# radio.net
KiCad netlist of a schematic drawn in Altium Designer
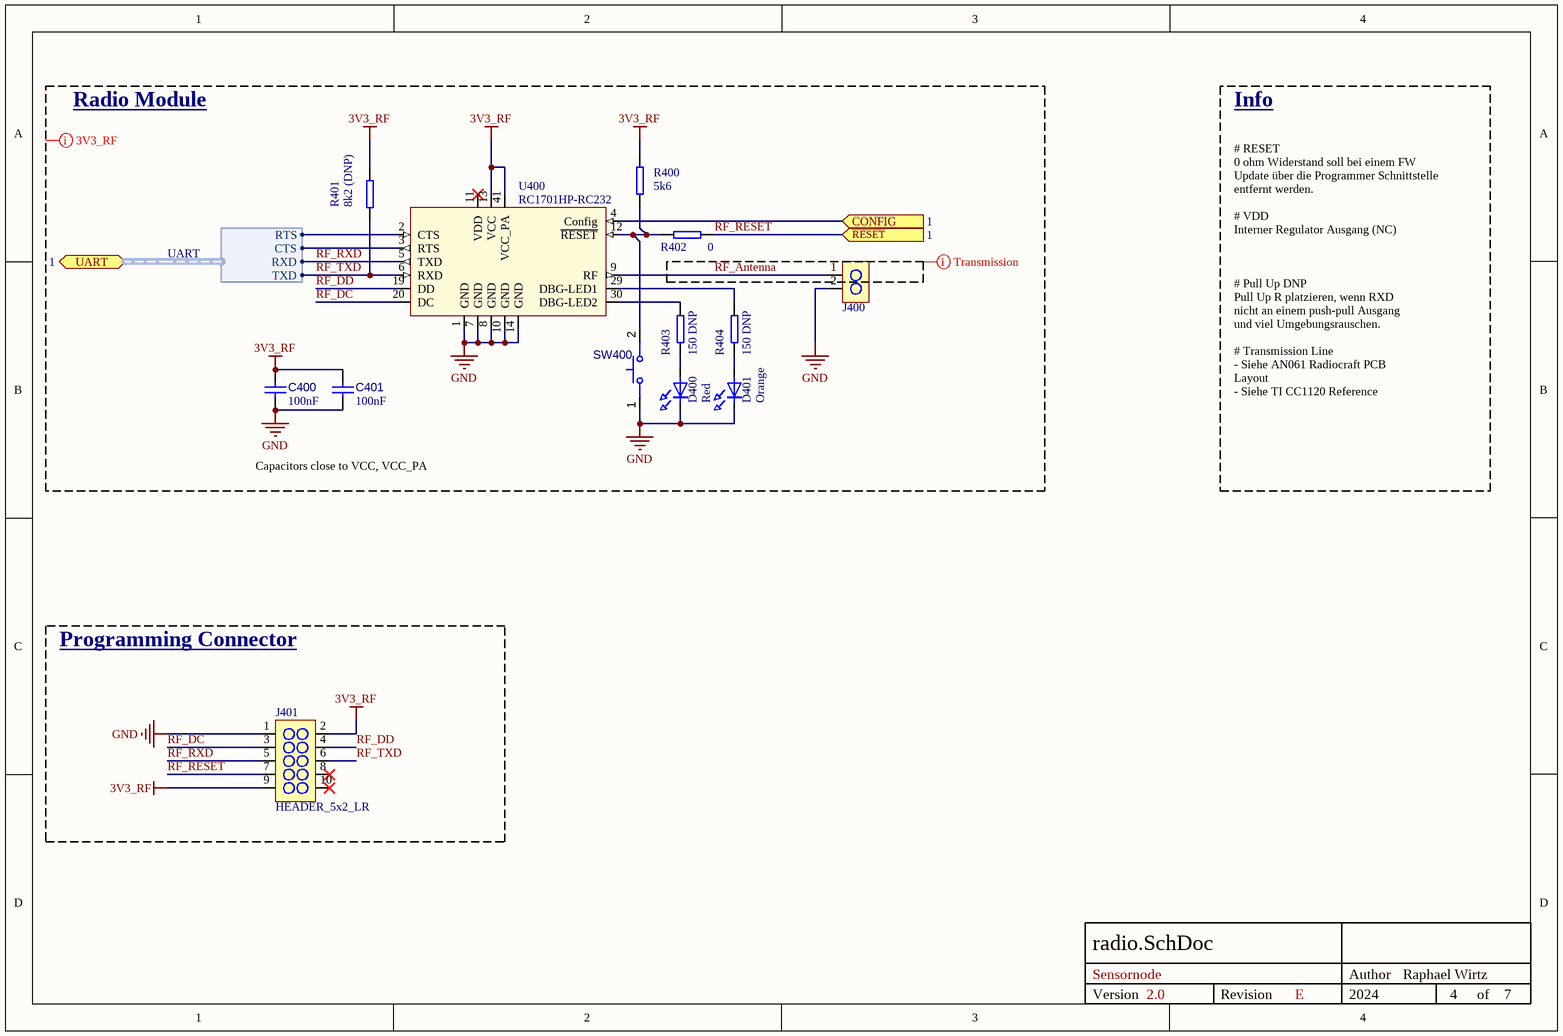
[diagram p0: radio.SchDoc]

(export (version "E")
  (design (tool "Eeschema 10.0.6"))
  (components
    (comp (ref "C400")
      (value "100nF")
      (footprint "sensornode:0603")
      (fields
        (field (name "TOLERANCE") "10%")
        (field (name "MANUFACTURER") "TDK")
        (field (name "MANUFACTURER PART NUMBER") "C1005X6S0J105K050BC")
      )
      (libsource (lib "sensornode_v2") (part "C"))
    )
    (comp (ref "C401")
      (value "100nF")
      (footprint "sensornode:0603")
      (fields
        (field (name "TOLERANCE") "10%")
        (field (name "MANUFACTURER") "TDK")
        (field (name "MANUFACTURER PART NUMBER") "C1005X6S0J105K050BC")
      )
      (libsource (lib "sensornode_v2") (part "C"))
    )
    (comp (ref "D400")
      (value "Red")
      (footprint "sensornode:0603-Diode")
      (libsource (lib "sensornode_v2") (part "LED_1"))
    )
    (comp (ref "D401")
      (value "Orange")
      (footprint "sensornode:0603-Diode")
      (libsource (lib "sensornode_v2") (part "LED_1"))
    )
    (comp (ref "J400")
      (value "RF_LPRS_x2")
      (footprint "sensornode:SMARACONNECTOR")
      (libsource (lib "sensornode_v2") (part "RF_LPRS_x2"))
    )
    (comp (ref "J401")
      (value "HEADER_5x2_LR")
      (footprint "sensornode:HEADER_SMD_1.27")
      (libsource (lib "sensornode_v2") (part "HEADER_5x2_LR"))
    )
    (comp (ref "R400")
      (value "5k6")
      (footprint "sensornode:0603")
      (description "Normaler Widerstand")
      (libsource (lib "sensornode_v2") (part "R?"))
    )
    (comp (ref "R401")
      (value "8k2 (DNP)")
      (footprint "sensornode:0603")
      (description "Normaler Widerstand")
      (libsource (lib "sensornode_v2") (part "R?"))
    )
    (comp (ref "R402")
      (value "0")
      (footprint "sensornode:0603")
      (description "Normaler Widerstand")
      (libsource (lib "sensornode_v2") (part "R?"))
    )
    (comp (ref "R403")
      (value "150 DNP")
      (footprint "sensornode:0603")
      (description "Normaler Widerstand")
      (libsource (lib "sensornode_v2") (part "R?"))
    )
    (comp (ref "R404")
      (value "150 DNP")
      (footprint "sensornode:0603")
      (description "Normaler Widerstand")
      (libsource (lib "sensornode_v2") (part "R?"))
    )
    (comp (ref "SW400")
      (value "B3U-1000P-B")
      (footprint "OMRON-B3U-1000P-2-B_V")
      (libsource (lib "Hochschule Luzern T&A") (part "CMP-00164-6"))
    )
    (comp (ref "U400")
      (value "RC1701HP-RC232")
      (footprint "sensornode:RF_RC1701HP")
      (libsource (lib "sensornode_v2") (part "RC1701HP-RC232"))
    )
  )
  (nets
    (net (code "2") (name "/CONFIG") (class "Default")
      (node (ref "U400") (pin "4") (pinfunction "Config_4") (pintype "input"))
    )
    (net (code "3") (name "/CTS") (class "Default")
      (node (ref "U400") (pin "3") (pinfunction "RTS_3") (pintype "output"))
    )
    (net (code "4") (name "/RF_Antenna") (class "Default")
      (node (ref "J400") (pin "1") (pinfunction "1_1") (pintype "passive"))
      (node (ref "U400") (pin "9") (pinfunction "RF_9") (pintype "output"))
    )
    (net (code "5") (name "/RF_DC") (class "Default")
      (node (ref "J401") (pin "3") (pinfunction "3_3") (pintype "passive"))
      (node (ref "U400") (pin "20") (pinfunction "DC_20") (pintype "passive"))
    )
    (net (code "6") (name "/RF_DD") (class "Default")
      (node (ref "J401") (pin "4") (pinfunction "4_4") (pintype "passive"))
      (node (ref "U400") (pin "19") (pinfunction "DD_19") (pintype "passive"))
    )
    (net (code "7") (name "/RF_RESET") (class "Default")
      (node (ref "J401") (pin "7") (pinfunction "7_7") (pintype "passive"))
      (node (ref "R402") (pin "1") (pintype "passive"))
    )
    (net (code "8") (name "/RF_RXD") (class "Default")
      (node (ref "J401") (pin "5") (pinfunction "5_5") (pintype "passive"))
      (node (ref "U400") (pin "5") (pinfunction "TXD_5") (pintype "output"))
    )
    (net (code "9") (name "/RF_TXD") (class "Default")
      (node (ref "J401") (pin "6") (pinfunction "6_6") (pintype "passive"))
      (node (ref "R401") (pin "1") (pintype "passive"))
      (node (ref "U400") (pin "6") (pinfunction "RXD_6") (pintype "input"))
    )
    (net (code "10") (name "/RTS") (class "Default")
      (node (ref "U400") (pin "2") (pinfunction "CTS_2") (pintype "input"))
    )
    (net (code "12") (name "3V3_RF") (class "Default")
      (node (ref "C400") (pin "2") (pinfunction "2_2") (pintype "passive"))
      (node (ref "C401") (pin "2") (pinfunction "2_2") (pintype "passive"))
      (node (ref "J401") (pin "2") (pinfunction "2_2") (pintype "passive"))
      (node (ref "J401") (pin "9") (pinfunction "9_9") (pintype "passive"))
      (node (ref "R400") (pin "2") (pintype "passive"))
      (node (ref "R401") (pin "2") (pintype "passive"))
      (node (ref "U400") (pin "13") (pinfunction "VCC_13") (pintype "passive"))
      (node (ref "U400") (pin "41") (pinfunction "VCC_PA_41") (pintype "passive"))
    )
    (net (code "13") (name "GND") (class "Default")
      (node (ref "C400") (pin "1") (pinfunction "1_1") (pintype "passive"))
      (node (ref "C401") (pin "1") (pinfunction "1_1") (pintype "passive"))
      (node (ref "D400") (pin "K") (pinfunction "K_K") (pintype "passive"))
      (node (ref "D401") (pin "K") (pinfunction "K_K") (pintype "passive"))
      (node (ref "J400") (pin "2") (pinfunction "2_2") (pintype "passive"))
      (node (ref "J401") (pin "1") (pinfunction "1_1") (pintype "passive"))
      (node (ref "SW400") (pin "1") (pinfunction "1_1") (pintype "passive"))
      (node (ref "U400") (pin "1") (pinfunction "GND_1") (pintype "passive"))
      (node (ref "U400") (pin "10") (pinfunction "GND_10") (pintype "passive"))
      (node (ref "U400") (pin "14") (pinfunction "GND_14") (pintype "passive"))
      (node (ref "U400") (pin "7") (pinfunction "GND_7") (pintype "passive"))
      (node (ref "U400") (pin "8") (pinfunction "GND_8") (pintype "passive"))
    )
    (net (code "14") (name "Net-(D400-PadA)") (class "Default")
      (node (ref "D400") (pin "A") (pinfunction "A_A") (pintype "passive"))
      (node (ref "R403") (pin "2") (pintype "passive"))
    )
    (net (code "15") (name "Net-(D401-PadA)") (class "Default")
      (node (ref "D401") (pin "A") (pinfunction "A_A") (pintype "passive"))
      (node (ref "R404") (pin "2") (pintype "passive"))
    )
    (net (code "16") (name "Net-(U400-DBG-LED1)") (class "Default")
      (node (ref "R404") (pin "1") (pintype "passive"))
      (node (ref "U400") (pin "29") (pinfunction "DBG-LED1_29") (pintype "passive"))
    )
    (net (code "17") (name "Net-(U400-DBG-LED2)") (class "Default")
      (node (ref "R403") (pin "1") (pintype "passive"))
      (node (ref "U400") (pin "30") (pinfunction "DBG-LED2_30") (pintype "passive"))
    )
    (net (code "18") (name "Net-(U400-RESET)") (class "Default")
      (node (ref "R400") (pin "1") (pintype "passive"))
      (node (ref "R402") (pin "2") (pintype "passive"))
      (node (ref "SW400") (pin "2") (pinfunction "2_2") (pintype "passive"))
      (node (ref "U400") (pin "12") (pinfunction "RESET_12") (pintype "input"))
    )
    (net (code "19") (name "unconnected-(J401-Pad8)") (class "Default")
      (node (ref "J401") (pin "8") (pinfunction "8_8") (pintype "passive+no_connect"))
    )
    (net (code "20") (name "unconnected-(J401-Pad10)") (class "Default")
      (node (ref "J401") (pin "10") (pinfunction "10_10") (pintype "passive+no_connect"))
    )
    (net (code "21") (name "unconnected-(U400-VDD-Pad11)") (class "Default")
      (node (ref "U400") (pin "11") (pinfunction "VDD_11") (pintype "passive+no_connect"))
    )
  )
)
